# main_board1.net
KiCad netlist of a schematic drawn in EAGLE
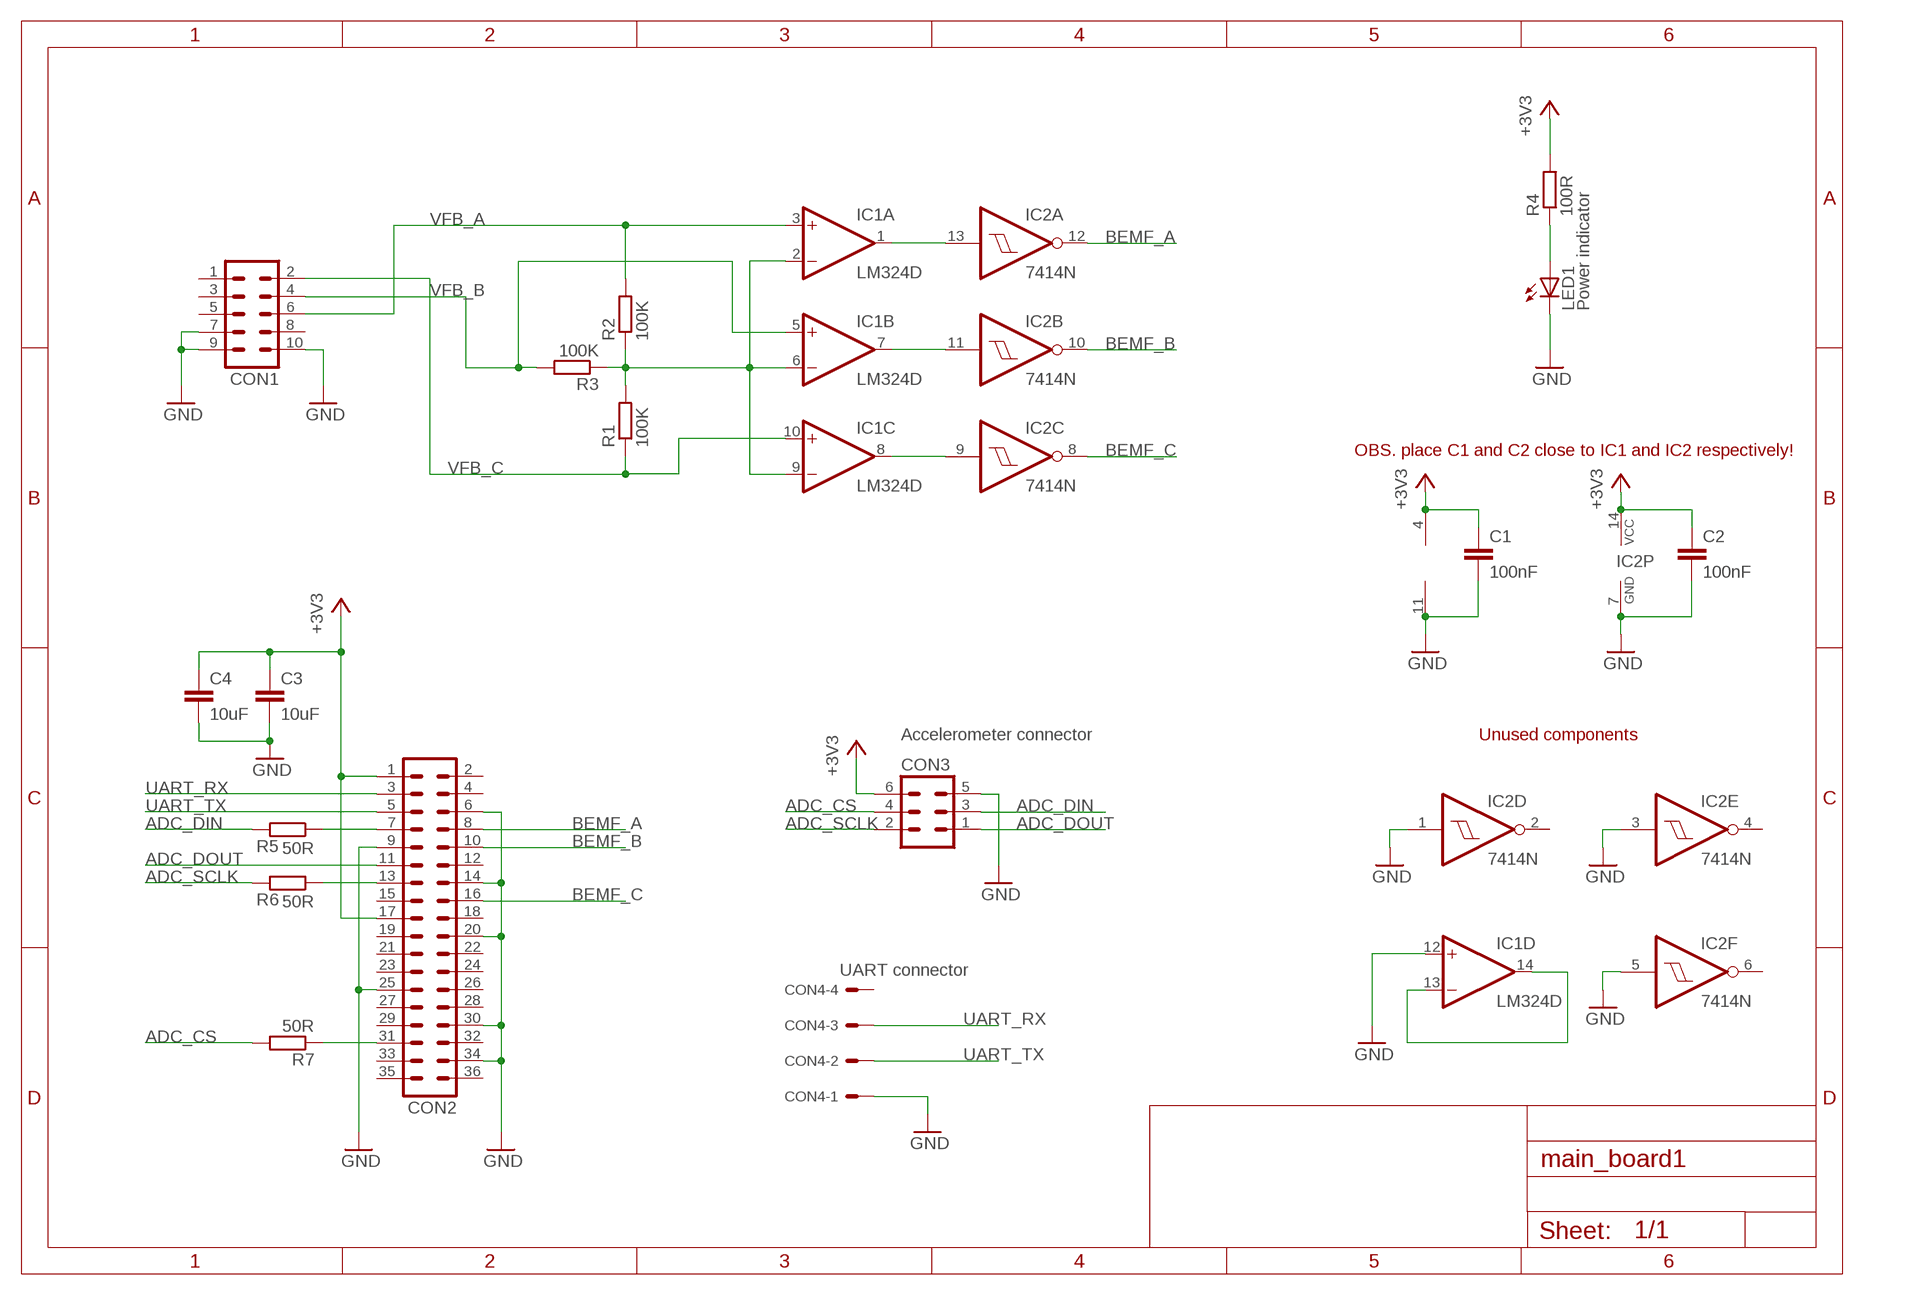
[diagram p0: schematic, sheet 1]

(export (version "E")
  (design (tool "Eeschema 10.0.6"))
  (components
    (comp (ref "C1")
      (value "100nF")
      (footprint "eagle-import:C0805K")
      (libsource (lib "eagle-import") (part "C-EUC0805K"))
    )
    (comp (ref "C2")
      (value "100nF")
      (footprint "eagle-import:C0805K")
      (libsource (lib "eagle-import") (part "C-EUC0805K"))
    )
    (comp (ref "C3")
      (value "10uF")
      (footprint "eagle-import:C1206K")
      (libsource (lib "eagle-import") (part "C-EUC1206K"))
    )
    (comp (ref "C4")
      (value "10uF")
      (footprint "eagle-import:C1206K")
      (libsource (lib "eagle-import") (part "C-EUC1206K"))
    )
    (comp (ref "CON1")
      (value "MA05-2")
      (footprint "eagle-import:MA05-2")
      (libsource (lib "eagle-import") (part "MA05-2"))
    )
    (comp (ref "CON2")
      (value "MA18-2")
      (footprint "eagle-import:MA18-2")
      (libsource (lib "eagle-import") (part "MA18-2"))
    )
    (comp (ref "CON3")
      (value "Accelerometer connector")
      (footprint "eagle-import:ML6")
      (libsource (lib "eagle-import") (part "ML6"))
    )
    (comp (ref "CON4")
      (value "UART connector")
      (footprint "eagle-import:6410-04")
      (libsource (lib "eagle-import") (part "22-?-0427-2041"))
    )
    (comp (ref "IC1")
      (value "LM324D")
      (footprint "eagle-import:SO14")
      (libsource (lib "eagle-import") (part "LM324D"))
    )
    (comp (ref "IC2")
      (value "7414N")
      (footprint "eagle-import:DIL14")
      (libsource (lib "eagle-import") (part "7414N"))
    )
    (comp (ref "LED1")
      (value "Power indicator")
      (footprint "eagle-import:CHIP-LED0805")
      (libsource (lib "eagle-import") (part "LEDCHIP-LED0805"))
    )
    (comp (ref "R1")
      (value "100K")
      (footprint "eagle-import:R1206")
      (libsource (lib "eagle-import") (part "R-EU_R1206"))
    )
    (comp (ref "R2")
      (value "100K")
      (footprint "eagle-import:R1206")
      (libsource (lib "eagle-import") (part "R-EU_R1206"))
    )
    (comp (ref "R3")
      (value "100K")
      (footprint "eagle-import:R1206")
      (libsource (lib "eagle-import") (part "R-EU_R1206"))
    )
    (comp (ref "R4")
      (value "100R")
      (footprint "eagle-import:R0805")
      (libsource (lib "eagle-import") (part "R-EU_R0805"))
    )
    (comp (ref "R5")
      (value "50R")
      (footprint "eagle-import:R0805")
      (libsource (lib "eagle-import") (part "R-EU_R0805"))
    )
    (comp (ref "R6")
      (value "50R")
      (footprint "eagle-import:R0805")
      (libsource (lib "eagle-import") (part "R-EU_R0805"))
    )
    (comp (ref "R7")
      (value "50R")
      (footprint "eagle-import:R0805")
      (libsource (lib "eagle-import") (part "R-EU_R0805"))
    )
  )
  (nets
    (net (code "1") (name "+3V3") (class "Default")
      (node (ref "C1") (pin "1") (pinfunction "1_1") (pintype "passive"))
      (node (ref "C2") (pin "1") (pinfunction "1_1") (pintype "passive"))
      (node (ref "C3") (pin "1") (pinfunction "1_1") (pintype "passive"))
      (node (ref "C4") (pin "1") (pinfunction "1_1") (pintype "passive"))
      (node (ref "CON2") (pin "1") (pinfunction "1_1") (pintype "passive"))
      (node (ref "CON2") (pin "17") (pinfunction "17_17") (pintype "passive"))
      (node (ref "CON3") (pin "6") (pinfunction "6_6") (pintype "passive"))
      (node (ref "IC1") (pin "4") (pinfunction "V+_4") (pintype "power_in"))
      (node (ref "IC2") (pin "14") (pinfunction "VCC_14") (pintype "power_in"))
      (node (ref "R4") (pin "2") (pinfunction "2_2") (pintype "passive"))
    )
    (net (code "2") (name "/ADC_CS") (class "Default")
      (node (ref "CON3") (pin "4") (pinfunction "4_4") (pintype "passive"))
      (node (ref "R7") (pin "2") (pinfunction "2_2") (pintype "passive"))
    )
    (net (code "3") (name "/ADC_DIN") (class "Default")
      (node (ref "CON3") (pin "3") (pinfunction "3_3") (pintype "passive"))
      (node (ref "R5") (pin "2") (pinfunction "2_2") (pintype "passive"))
    )
    (net (code "4") (name "/ADC_DOUT") (class "Default")
      (node (ref "CON2") (pin "11") (pinfunction "11_11") (pintype "passive"))
      (node (ref "CON3") (pin "1") (pinfunction "1_1") (pintype "passive"))
    )
    (net (code "5") (name "/ADC_SCLK") (class "Default")
      (node (ref "CON3") (pin "2") (pinfunction "2_2") (pintype "passive"))
      (node (ref "R6") (pin "2") (pinfunction "2_2") (pintype "passive"))
    )
    (net (code "6") (name "/BEMF_A") (class "Default")
      (node (ref "CON2") (pin "8") (pinfunction "8_8") (pintype "passive"))
      (node (ref "IC2") (pin "12") (pinfunction "O_12") (pintype "output"))
    )
    (net (code "7") (name "/BEMF_B") (class "Default")
      (node (ref "CON2") (pin "10") (pinfunction "10_10") (pintype "passive"))
      (node (ref "IC2") (pin "10") (pinfunction "O_10") (pintype "output"))
    )
    (net (code "8") (name "/BEMF_C") (class "Default")
      (node (ref "CON2") (pin "16") (pinfunction "16_16") (pintype "passive"))
      (node (ref "IC2") (pin "8") (pinfunction "O_8") (pintype "output"))
    )
    (net (code "9") (name "/UART_RX") (class "Default")
      (node (ref "CON2") (pin "3") (pinfunction "3_3") (pintype "passive"))
      (node (ref "CON4") (pin "3") (pinfunction "S_3") (pintype "passive"))
    )
    (net (code "10") (name "/UART_TX") (class "Default")
      (node (ref "CON2") (pin "5") (pinfunction "5_5") (pintype "passive"))
      (node (ref "CON4") (pin "2") (pinfunction "S_2") (pintype "passive"))
    )
    (net (code "11") (name "/VFB_A") (class "Default")
      (node (ref "CON1") (pin "6") (pinfunction "6_6") (pintype "passive"))
      (node (ref "IC1") (pin "3") (pinfunction "+IN_3") (pintype "input"))
      (node (ref "R2") (pin "2") (pinfunction "2_2") (pintype "passive"))
    )
    (net (code "12") (name "/VFB_B") (class "Default")
      (node (ref "CON1") (pin "4") (pinfunction "4_4") (pintype "passive"))
      (node (ref "IC1") (pin "5") (pinfunction "+IN_5") (pintype "input"))
      (node (ref "R3") (pin "2") (pinfunction "2_2") (pintype "passive"))
    )
    (net (code "13") (name "/VFB_C") (class "Default")
      (node (ref "CON1") (pin "2") (pinfunction "2_2") (pintype "passive"))
      (node (ref "IC1") (pin "10") (pinfunction "+IN_10") (pintype "input"))
      (node (ref "R1") (pin "1") (pinfunction "1_1") (pintype "passive"))
    )
    (net (code "14") (name "GND") (class "Default")
      (node (ref "C1") (pin "2") (pinfunction "2_2") (pintype "passive"))
      (node (ref "C2") (pin "2") (pinfunction "2_2") (pintype "passive"))
      (node (ref "C3") (pin "2") (pinfunction "2_2") (pintype "passive"))
      (node (ref "C4") (pin "2") (pinfunction "2_2") (pintype "passive"))
      (node (ref "CON1") (pin "10") (pinfunction "10_10") (pintype "passive"))
      (node (ref "CON1") (pin "7") (pinfunction "7_7") (pintype "passive"))
      (node (ref "CON1") (pin "9") (pinfunction "9_9") (pintype "passive"))
      (node (ref "CON2") (pin "14") (pinfunction "14_14") (pintype "passive"))
      (node (ref "CON2") (pin "20") (pinfunction "20_20") (pintype "passive"))
      (node (ref "CON2") (pin "25") (pinfunction "25_25") (pintype "passive"))
      (node (ref "CON2") (pin "30") (pinfunction "30_30") (pintype "passive"))
      (node (ref "CON2") (pin "34") (pinfunction "34_34") (pintype "passive"))
      (node (ref "CON2") (pin "6") (pinfunction "6_6") (pintype "passive"))
      (node (ref "CON2") (pin "9") (pinfunction "9_9") (pintype "passive"))
      (node (ref "CON3") (pin "5") (pinfunction "5_5") (pintype "passive"))
      (node (ref "CON4") (pin "1") (pinfunction "S_1") (pintype "passive"))
      (node (ref "IC1") (pin "11") (pinfunction "V-_11") (pintype "power_in"))
      (node (ref "IC1") (pin "12") (pinfunction "+IN_12") (pintype "input"))
      (node (ref "IC2") (pin "1") (pinfunction "I_1") (pintype "input"))
      (node (ref "IC2") (pin "3") (pinfunction "I_3") (pintype "input"))
      (node (ref "IC2") (pin "5") (pinfunction "I_5") (pintype "input"))
      (node (ref "IC2") (pin "7") (pinfunction "GND_7") (pintype "power_in"))
      (node (ref "LED1") (pin "C") (pinfunction "C_C") (pintype "passive"))
    )
    (net (code "15") (name "Net-(CON2-Pad7)") (class "Default")
      (node (ref "CON2") (pin "7") (pinfunction "7_7") (pintype "passive"))
      (node (ref "R5") (pin "1") (pinfunction "1_1") (pintype "passive"))
    )
    (net (code "16") (name "Net-(CON2-Pad13)") (class "Default")
      (node (ref "CON2") (pin "13") (pinfunction "13_13") (pintype "passive"))
      (node (ref "R6") (pin "1") (pinfunction "1_1") (pintype "passive"))
    )
    (net (code "17") (name "Net-(CON2-Pad31)") (class "Default")
      (node (ref "CON2") (pin "31") (pinfunction "31_31") (pintype "passive"))
      (node (ref "R7") (pin "1") (pinfunction "1_1") (pintype "passive"))
    )
    (net (code "18") (name "Net-(IC1A--IN)") (class "Default")
      (node (ref "IC1") (pin "2") (pinfunction "-IN_2") (pintype "input"))
      (node (ref "IC1") (pin "6") (pinfunction "-IN_6") (pintype "input"))
      (node (ref "IC1") (pin "9") (pinfunction "-IN_9") (pintype "input"))
      (node (ref "R1") (pin "2") (pinfunction "2_2") (pintype "passive"))
      (node (ref "R2") (pin "1") (pinfunction "1_1") (pintype "passive"))
      (node (ref "R3") (pin "1") (pinfunction "1_1") (pintype "passive"))
    )
    (net (code "19") (name "Net-(IC1A-OUT)") (class "Default")
      (node (ref "IC1") (pin "1") (pinfunction "OUT_1") (pintype "output"))
      (node (ref "IC2") (pin "13") (pinfunction "I_13") (pintype "input"))
    )
    (net (code "20") (name "Net-(IC1B-OUT)") (class "Default")
      (node (ref "IC1") (pin "7") (pinfunction "OUT_7") (pintype "output"))
      (node (ref "IC2") (pin "11") (pinfunction "I_11") (pintype "input"))
    )
    (net (code "21") (name "Net-(IC1C-OUT)") (class "Default")
      (node (ref "IC1") (pin "8") (pinfunction "OUT_8") (pintype "output"))
      (node (ref "IC2") (pin "9") (pinfunction "I_9") (pintype "input"))
    )
    (net (code "22") (name "Net-(IC1D--IN)") (class "Default")
      (node (ref "IC1") (pin "13") (pinfunction "-IN_13") (pintype "input"))
      (node (ref "IC1") (pin "14") (pinfunction "OUT_14") (pintype "output"))
    )
    (net (code "23") (name "Net-(LED1-PadA)") (class "Default")
      (node (ref "LED1") (pin "A") (pinfunction "A_A") (pintype "passive"))
      (node (ref "R4") (pin "1") (pinfunction "1_1") (pintype "passive"))
    )
    (net (code "24") (name "unconnected-(CON1-Pad1)") (class "Default")
      (node (ref "CON1") (pin "1") (pinfunction "1_1") (pintype "passive"))
    )
    (net (code "25") (name "unconnected-(CON1-Pad3)") (class "Default")
      (node (ref "CON1") (pin "3") (pinfunction "3_3") (pintype "passive"))
    )
    (net (code "26") (name "unconnected-(CON1-Pad5)") (class "Default")
      (node (ref "CON1") (pin "5") (pinfunction "5_5") (pintype "passive"))
    )
    (net (code "27") (name "unconnected-(CON1-Pad8)") (class "Default")
      (node (ref "CON1") (pin "8") (pinfunction "8_8") (pintype "passive"))
    )
    (net (code "28") (name "unconnected-(CON2-Pad2)") (class "Default")
      (node (ref "CON2") (pin "2") (pinfunction "2_2") (pintype "passive"))
    )
    (net (code "29") (name "unconnected-(CON2-Pad4)") (class "Default")
      (node (ref "CON2") (pin "4") (pinfunction "4_4") (pintype "passive"))
    )
    (net (code "30") (name "unconnected-(CON2-Pad12)") (class "Default")
      (node (ref "CON2") (pin "12") (pinfunction "12_12") (pintype "passive"))
    )
    (net (code "31") (name "unconnected-(CON2-Pad15)") (class "Default")
      (node (ref "CON2") (pin "15") (pinfunction "15_15") (pintype "passive"))
    )
    (net (code "32") (name "unconnected-(CON2-Pad18)") (class "Default")
      (node (ref "CON2") (pin "18") (pinfunction "18_18") (pintype "passive"))
    )
    (net (code "33") (name "unconnected-(CON2-Pad19)") (class "Default")
      (node (ref "CON2") (pin "19") (pinfunction "19_19") (pintype "passive"))
    )
    (net (code "34") (name "unconnected-(CON2-Pad21)") (class "Default")
      (node (ref "CON2") (pin "21") (pinfunction "21_21") (pintype "passive"))
    )
    (net (code "35") (name "unconnected-(CON2-Pad22)") (class "Default")
      (node (ref "CON2") (pin "22") (pinfunction "22_22") (pintype "passive"))
    )
    (net (code "36") (name "unconnected-(CON2-Pad23)") (class "Default")
      (node (ref "CON2") (pin "23") (pinfunction "23_23") (pintype "passive"))
    )
    (net (code "37") (name "unconnected-(CON2-Pad24)") (class "Default")
      (node (ref "CON2") (pin "24") (pinfunction "24_24") (pintype "passive"))
    )
    (net (code "38") (name "unconnected-(CON2-Pad26)") (class "Default")
      (node (ref "CON2") (pin "26") (pinfunction "26_26") (pintype "passive"))
    )
    (net (code "39") (name "unconnected-(CON2-Pad27)") (class "Default")
      (node (ref "CON2") (pin "27") (pinfunction "27_27") (pintype "passive"))
    )
    (net (code "40") (name "unconnected-(CON2-Pad28)") (class "Default")
      (node (ref "CON2") (pin "28") (pinfunction "28_28") (pintype "passive"))
    )
    (net (code "41") (name "unconnected-(CON2-Pad29)") (class "Default")
      (node (ref "CON2") (pin "29") (pinfunction "29_29") (pintype "passive"))
    )
    (net (code "42") (name "unconnected-(CON2-Pad32)") (class "Default")
      (node (ref "CON2") (pin "32") (pinfunction "32_32") (pintype "passive"))
    )
    (net (code "43") (name "unconnected-(CON2-Pad33)") (class "Default")
      (node (ref "CON2") (pin "33") (pinfunction "33_33") (pintype "passive"))
    )
    (net (code "44") (name "unconnected-(CON2-Pad35)") (class "Default")
      (node (ref "CON2") (pin "35") (pinfunction "35_35") (pintype "passive"))
    )
    (net (code "45") (name "unconnected-(CON2-Pad36)") (class "Default")
      (node (ref "CON2") (pin "36") (pinfunction "36_36") (pintype "passive"))
    )
    (net (code "46") (name "unconnected-(CON4D-S-Pad4)") (class "Default")
      (node (ref "CON4") (pin "4") (pinfunction "S_4") (pintype "passive"))
    )
    (net (code "47") (name "unconnected-(IC2D-O-Pad2)") (class "Default")
      (node (ref "IC2") (pin "2") (pinfunction "O_2") (pintype "output"))
    )
    (net (code "48") (name "unconnected-(IC2E-O-Pad4)") (class "Default")
      (node (ref "IC2") (pin "4") (pinfunction "O_4") (pintype "output"))
    )
    (net (code "49") (name "unconnected-(IC2F-O-Pad6)") (class "Default")
      (node (ref "IC2") (pin "6") (pinfunction "O_6") (pintype "output"))
    )
  )
)
